# AdelinoR1.net
KiCad netlist of a schematic drawn in EAGLE
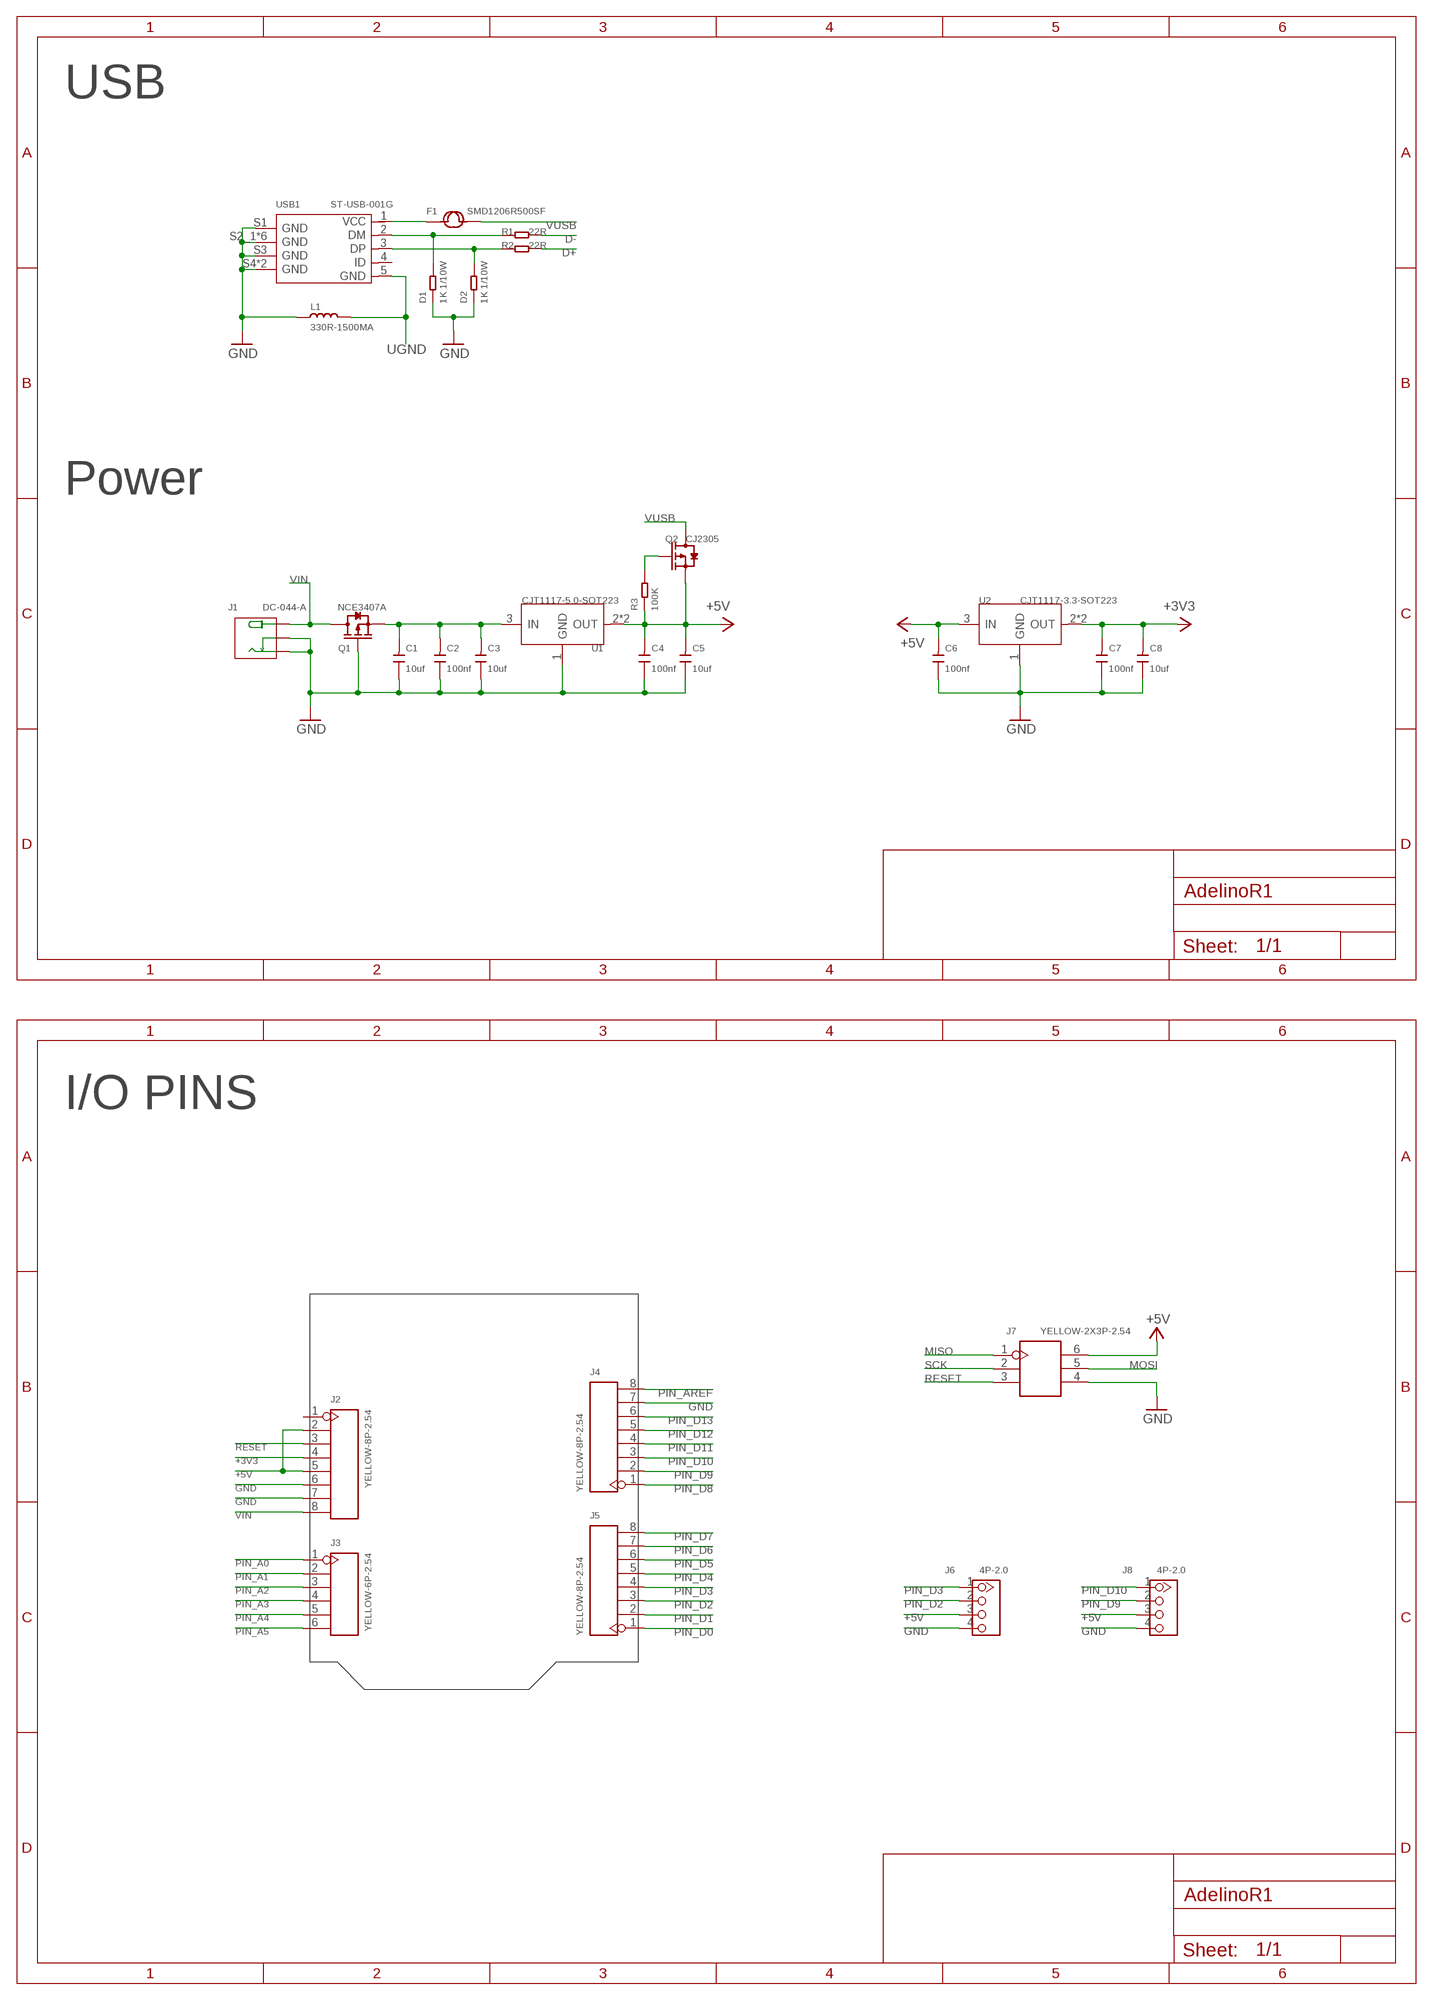
[diagram p0: schematic, sheet 1, part 1 of 2]
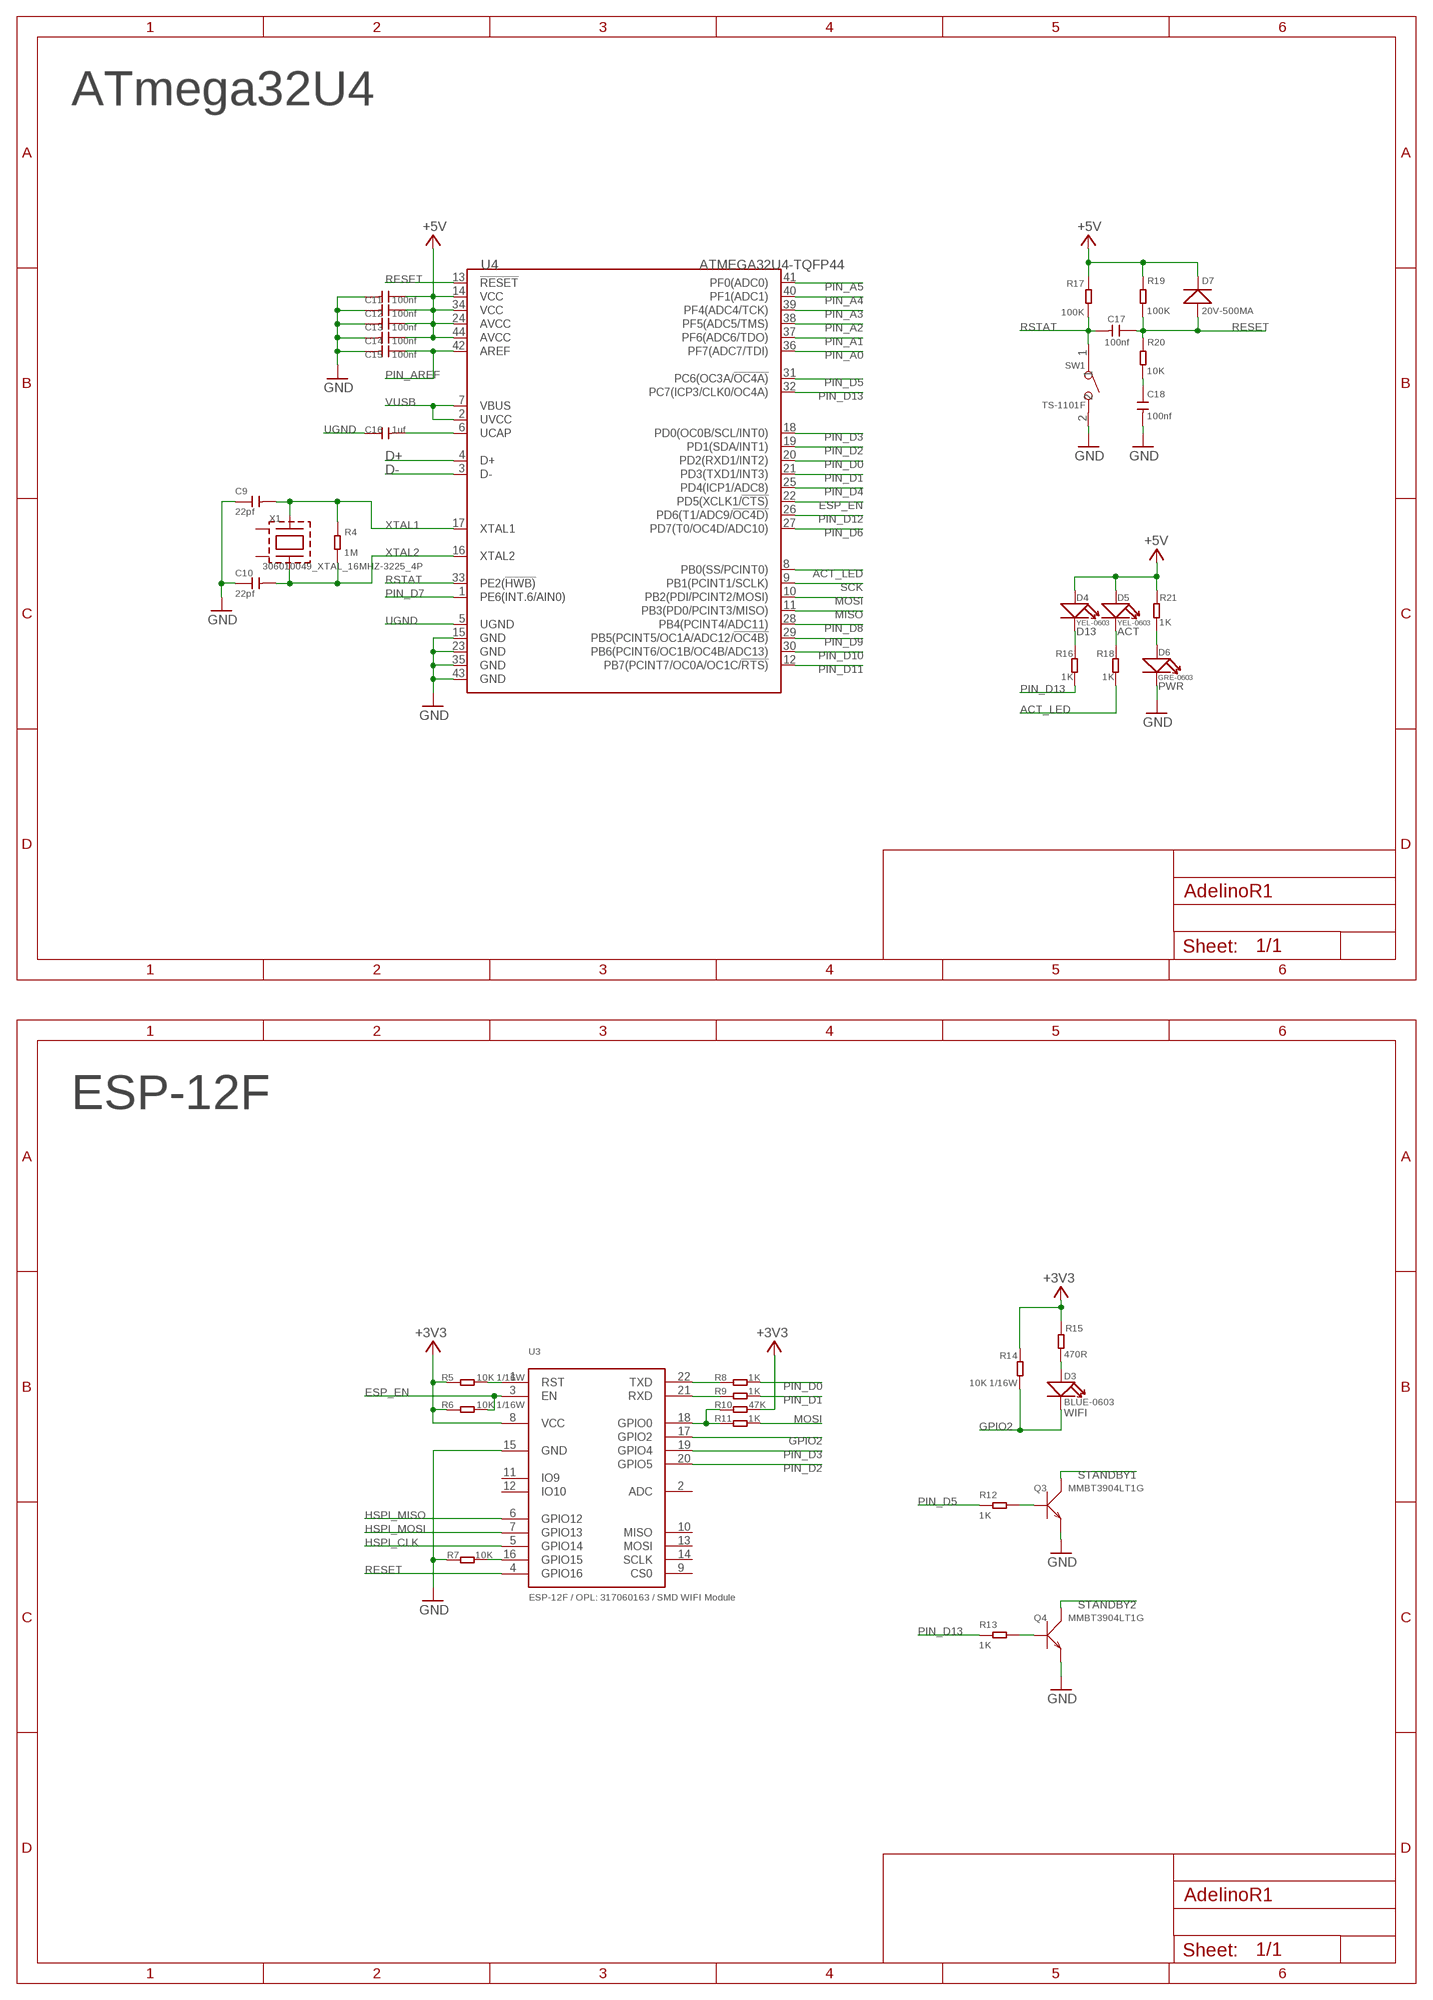
[diagram p1: schematic, sheet 1, part 2 of 2]

(export (version "E")
  (design (tool "Eeschema 10.0.6"))
  (components
    (comp (ref "C1")
      (value "10uf")
      (footprint "eagle-import:C0805")
      (fields (field (name "MPN") "CC0805KKX5R8BB106"))
      (libsource (lib "eagle-import") (part "CERAMIC-10UF-25V-10%-X5R(0805)"))
    )
    (comp (ref "C2")
      (value "100nf")
      (footprint "eagle-import:C0402")
      (fields (field (name "MPN") "CC0402KRX7R8BB104"))
      (libsource (lib "eagle-import") (part "CERAMIC-100NF-25V-10%-X7R(0402)"))
    )
    (comp (ref "C3")
      (value "10uf")
      (footprint "eagle-import:C0805")
      (fields (field (name "MPN") "CC0805KKX5R8BB106"))
      (libsource (lib "eagle-import") (part "CERAMIC-10UF-25V-10%-X5R(0805)"))
    )
    (comp (ref "C4")
      (value "100nf")
      (footprint "eagle-import:C0402")
      (fields (field (name "MPN") "CC0402KRX7R8BB104"))
      (libsource (lib "eagle-import") (part "CERAMIC-100NF-25V-10%-X7R(0402)"))
    )
    (comp (ref "C5")
      (value "10uf")
      (footprint "eagle-import:C0805")
      (fields (field (name "MPN") "CC0805KKX5R8BB106"))
      (libsource (lib "eagle-import") (part "CERAMIC-10UF-25V-10%-X5R(0805)"))
    )
    (comp (ref "C6")
      (value "100nf")
      (footprint "eagle-import:C0402")
      (fields (field (name "MPN") "CC0402KRX7R8BB104"))
      (libsource (lib "eagle-import") (part "CERAMIC-100NF-25V-10%-X7R(0402)"))
    )
    (comp (ref "C7")
      (value "100nf")
      (footprint "eagle-import:C0402")
      (fields (field (name "MPN") "CC0402KRX7R8BB104"))
      (libsource (lib "eagle-import") (part "CERAMIC-100NF-25V-10%-X7R(0402)"))
    )
    (comp (ref "C8")
      (value "10uf")
      (footprint "eagle-import:C0805")
      (fields (field (name "MPN") "CC0805KKX5R8BB106"))
      (libsource (lib "eagle-import") (part "CERAMIC-10UF-25V-10%-X5R(0805)"))
    )
    (comp (ref "C9")
      (value "22pf")
      (footprint "eagle-import:C0402")
      (fields (field (name "MPN") "CC0402JRNPO9BN220"))
      (libsource (lib "eagle-import") (part "CERAMIC-22PF-50V-5%-NPO(0402)"))
    )
    (comp (ref "C10")
      (value "22pf")
      (footprint "eagle-import:C0402")
      (fields (field (name "MPN") "CC0402JRNPO9BN220"))
      (libsource (lib "eagle-import") (part "CERAMIC-22PF-50V-5%-NPO(0402)"))
    )
    (comp (ref "C11")
      (value "100nf")
      (footprint "eagle-import:C0402")
      (fields (field (name "MPN") "CC0402KRX7R8BB104"))
      (libsource (lib "eagle-import") (part "CERAMIC-100NF-25V-10%-X7R(0402)"))
    )
    (comp (ref "C12")
      (value "100nf")
      (footprint "eagle-import:C0402")
      (fields (field (name "MPN") "CC0402KRX7R8BB104"))
      (libsource (lib "eagle-import") (part "CERAMIC-100NF-25V-10%-X7R(0402)"))
    )
    (comp (ref "C13")
      (value "100nf")
      (footprint "eagle-import:C0402")
      (fields (field (name "MPN") "CC0402KRX7R8BB104"))
      (libsource (lib "eagle-import") (part "CERAMIC-100NF-25V-10%-X7R(0402)"))
    )
    (comp (ref "C14")
      (value "100nf")
      (footprint "eagle-import:C0402")
      (fields (field (name "MPN") "CC0402KRX7R8BB104"))
      (libsource (lib "eagle-import") (part "CERAMIC-100NF-25V-10%-X7R(0402)"))
    )
    (comp (ref "C15")
      (value "100nf")
      (footprint "eagle-import:C0402")
      (fields (field (name "MPN") "CC0402KRX7R8BB104"))
      (libsource (lib "eagle-import") (part "CERAMIC-100NF-25V-10%-X7R(0402)"))
    )
    (comp (ref "C16")
      (value "1uf")
      (footprint "eagle-import:C0805")
      (fields (field (name "MPN") "CC0805KKX7R8BB105"))
      (libsource (lib "eagle-import") (part "CERAMIC-1UF-25V-10%-X7R(0805)"))
    )
    (comp (ref "C17")
      (value "100nf")
      (footprint "eagle-import:C0402")
      (fields (field (name "MPN") "CC0402KRX7R8BB104"))
      (libsource (lib "eagle-import") (part "CERAMIC-100NF-25V-10%-X7R(0402)"))
    )
    (comp (ref "C18")
      (value "100nf")
      (footprint "eagle-import:C0402")
      (fields (field (name "MPN") "CC0402KRX7R8BB104"))
      (libsource (lib "eagle-import") (part "CERAMIC-100NF-25V-10%-X7R(0402)"))
    )
    (comp (ref "D1")
      (value "1K 1/10W")
      (footprint "eagle-import:D0603")
      (fields (field (name "MPN") "RC0603JR-071KL"))
      (libsource (lib "eagle-import") (part "SMD-ESD-CG0603MLC-05E"))
    )
    (comp (ref "D2")
      (value "1K 1/10W")
      (footprint "eagle-import:D0603")
      (fields (field (name "MPN") "RC0603JR-071KL"))
      (libsource (lib "eagle-import") (part "SMD-ESD-CG0603MLC-05E"))
    )
    (comp (ref "D3")
      (value "BLUE-0603")
      (footprint "eagle-import:LED-0603")
      (fields (field (name "MPN") "19-217-BHC-ZL1M2RY-3T") (field (name "LABEL") "WIFI"))
      (libsource (lib "eagle-import") (part "SMD-LED-CLEAR-BLUE(0603)"))
    )
    (comp (ref "D4")
      (value "YEL-0603")
      (footprint "eagle-import:LED-0603")
      (fields (field (name "MPN") "19-217-Y5C-AM1N1VY-3T") (field (name "LABEL") "D13"))
      (libsource (lib "eagle-import") (part "SMD-LED-CLEAR-YELLOW(0603)"))
    )
    (comp (ref "D5")
      (value "YEL-0603")
      (footprint "eagle-import:LED-0603")
      (fields (field (name "MPN") "19-217-Y5C-AM1N1VY-3T") (field (name "LABEL") "ACT"))
      (libsource (lib "eagle-import") (part "SMD-LED-CLEAR-YELLOW(0603)"))
    )
    (comp (ref "D6")
      (value "GRE-0603")
      (footprint "eagle-import:LED-0603")
      (fields (field (name "MPN") "19-217-G7C-AN1P2-3T") (field (name "LABEL") "PWR"))
      (libsource (lib "eagle-import") (part "SMD-LED-CLEAR-GREEN(0603)"))
    )
    (comp (ref "D7")
      (value "20V-500MA")
      (footprint "eagle-import:SOD-123")
      (fields (field (name "MPN") "MBR0520LT1G"))
      (libsource (lib "eagle-import") (part "SMD-DIODE-SCHOTTKY-20V-500MA(SOD-123)P"))
    )
    (comp (ref "F1")
      (value "SMD1206R500SF")
      (footprint "eagle-import:F1206")
      (libsource (lib "eagle-import") (part "SMD-PPTC-500MA(1206)"))
    )
    (comp (ref "J1")
      (value "DC-044-A")
      (footprint "eagle-import:DCJ3P-11.6X9.6X7.0MM")
      (fields (field (name "MPN") "JACK-DC-044-A"))
      (libsource (lib "eagle-import") (part "JACK-DC-044-A"))
    )
    (comp (ref "J2")
      (value "YELLOW-8P-2.54")
      (footprint "eagle-import:H8-2.54")
      (fields (field (name "MPN") "F185-1108A1BSYC1"))
      (libsource (lib "eagle-import") (part "DIP-YELLOW-FEMALE-HEADER(8P-2.54)"))
    )
    (comp (ref "J3")
      (value "YELLOW-6P-2.54")
      (footprint "eagle-import:H6-2.54")
      (fields (field (name "MPN") "F185-1106A1BSYA3"))
      (libsource (lib "eagle-import") (part "DIP-YELLOW-FEMALE-HEADER-VERT(6P-2.54)"))
    )
    (comp (ref "J4")
      (value "YELLOW-8P-2.54")
      (footprint "eagle-import:H8-2.54")
      (fields (field (name "MPN") "F185-1108A1BSYC1"))
      (libsource (lib "eagle-import") (part "DIP-YELLOW-FEMALE-HEADER(8P-2.54)"))
    )
    (comp (ref "J5")
      (value "YELLOW-8P-2.54")
      (footprint "eagle-import:H8-2.54")
      (fields (field (name "MPN") "F185-1108A1BSYC1"))
      (libsource (lib "eagle-import") (part "DIP-YELLOW-FEMALE-HEADER(8P-2.54)"))
    )
    (comp (ref "J6")
      (value "4P-2.0")
      (footprint "eagle-import:HW4-2.0")
      (libsource (lib "eagle-import") (part "GROVE-CONNECTOR-DIP(4P-2.0)"))
    )
    (comp (ref "J7")
      (value "YELLOW-2X3P-2.54")
      (footprint "eagle-import:H2X3-2.54")
      (fields (field (name "MPN") "P125-1203A0BS116A2"))
      (libsource (lib "eagle-import") (part "DIP-YELLOW-MALE-HEADER-VERT(2X3P-2.54)"))
    )
    (comp (ref "J8")
      (value "4P-2.0")
      (footprint "eagle-import:HW4-2.0")
      (libsource (lib "eagle-import") (part "GROVE-CONNECTOR-DIP(4P-2.0)"))
    )
    (comp (ref "L1")
      (value "330R-1500MA")
      (footprint "eagle-import:L0805")
      (fields (field (name "MPN") "BLM21PG331SN1D"))
      (libsource (lib "eagle-import") (part "SMD-FERRITE-BEAD-330R-1500MA(0805)'0805'"))
    )
    (comp (ref "Q1")
      (value "NCE3407A")
      (footprint "eagle-import:SOT-23")
      (libsource (lib "eagle-import") (part "SMD-MOSFET-P-CH-VDC=30V-ID=4.3A-NCE3407A(SOT-23)"))
    )
    (comp (ref "Q2")
      (value "CJ2305")
      (footprint "eagle-import:SOT-23")
      (libsource (lib "eagle-import") (part "SMD-MOSFET-P-CH-8V-4.1A-CJ2305(SOT-23)"))
    )
    (comp (ref "Q3")
      (value "MMBT3904LT1G")
      (footprint "eagle-import:SOT-23")
      (libsource (lib "eagle-import") (part "SMD-TRANSISTORS-NPN-40V-200MA-MMBT3904LT1G(SOT-23)"))
    )
    (comp (ref "Q4")
      (value "MMBT3904LT1G")
      (footprint "eagle-import:SOT-23")
      (libsource (lib "eagle-import") (part "SMD-TRANSISTORS-NPN-40V-200MA-MMBT3904LT1G(SOT-23)"))
    )
    (comp (ref "R1")
      (value "22R")
      (footprint "eagle-import:R0402")
      (fields (field (name "MPN") "RC0402FR-0722RL"))
      (libsource (lib "eagle-import") (part "SMD-RES-22R-1%-1/16W(0402)"))
    )
    (comp (ref "R2")
      (value "22R")
      (footprint "eagle-import:R0402")
      (fields (field (name "MPN") "RC0402FR-0722RL"))
      (libsource (lib "eagle-import") (part "SMD-RES-22R-1%-1/16W(0402)"))
    )
    (comp (ref "R3")
      (value "100K")
      (footprint "eagle-import:R0402")
      (fields (field (name "MPN") "RC0402FR-07100KL"))
      (libsource (lib "eagle-import") (part "SMD-RES-100K-1%-1/16W(0402)"))
    )
    (comp (ref "R4")
      (value "1M")
      (footprint "eagle-import:R0402")
      (fields (field (name "MPN") "RC0402FR-071ML"))
      (libsource (lib "eagle-import") (part "SMD-RES-1M-1%-1/16W(0402)"))
    )
    (comp (ref "R5")
      (value "10K 1/16W")
      (footprint "eagle-import:R0402")
      (fields (field (name "MPN") "RC0402FR-0710KL"))
      (libsource (lib "eagle-import") (part "SMD-RES-10K-1%-1/16W(0402)"))
    )
    (comp (ref "R6")
      (value "10K 1/16W")
      (footprint "eagle-import:R0402")
      (fields (field (name "MPN") "RC0402FR-0710KL"))
      (libsource (lib "eagle-import") (part "SMD-RES-10K-1%-1/16W(0402)"))
    )
    (comp (ref "R7")
      (value "10K")
      (footprint "eagle-import:R0402")
      (fields (field (name "MPN") "RC0402FR-0710KL"))
      (libsource (lib "eagle-import") (part "SMD-RES-10K-1%-1/16W(0402)"))
    )
    (comp (ref "R8")
      (value "1K")
      (footprint "eagle-import:R0402")
      (fields (field (name "MPN") "RC0402JR-071KL"))
      (libsource (lib "eagle-import") (part "SMD-RES-1K-5%-1/16W(0402)"))
    )
    (comp (ref "R9")
      (value "1K")
      (footprint "eagle-import:R0402")
      (fields (field (name "MPN") "RC0402JR-071KL"))
      (libsource (lib "eagle-import") (part "SMD-RES-1K-5%-1/16W(0402)"))
    )
    (comp (ref "R10")
      (value "47K")
      (footprint "eagle-import:R0402")
      (fields (field (name "MPN") "RC0402JR-0747KL"))
      (libsource (lib "eagle-import") (part "SMD-RES-47K-5%-1/16W(0402)"))
    )
    (comp (ref "R11")
      (value "1K")
      (footprint "eagle-import:R0402")
      (fields (field (name "MPN") "RC0402JR-071KL"))
      (libsource (lib "eagle-import") (part "SMD-RES-1K-5%-1/16W(0402)"))
    )
    (comp (ref "R12")
      (value "1K")
      (footprint "eagle-import:R0402")
      (fields (field (name "MPN") "RC0402JR-071KL"))
      (libsource (lib "eagle-import") (part "SMD-RES-1K-5%-1/16W(0402)"))
    )
    (comp (ref "R13")
      (value "1K")
      (footprint "eagle-import:R0402")
      (fields (field (name "MPN") "RC0402JR-071KL"))
      (libsource (lib "eagle-import") (part "SMD-RES-1K-5%-1/16W(0402)"))
    )
    (comp (ref "R14")
      (value "10K 1/16W")
      (footprint "eagle-import:R0402")
      (fields (field (name "MPN") "RC0402FR-0710KL"))
      (libsource (lib "eagle-import") (part "SMD-RES-10K-1%-1/16W(0402)"))
    )
    (comp (ref "R15")
      (value "470R")
      (footprint "eagle-import:R0402")
      (fields (field (name "MPN") "RC0402JR-07470RL"))
      (libsource (lib "eagle-import") (part "SMD-RES-470R-5%-1/16W(0402)"))
    )
    (comp (ref "R16")
      (value "1K")
      (footprint "eagle-import:R0402")
      (fields (field (name "MPN") "RC0402JR-071KL"))
      (libsource (lib "eagle-import") (part "SMD-RES-1K-5%-1/16W(0402)"))
    )
    (comp (ref "R17")
      (value "100K")
      (footprint "eagle-import:R0402")
      (fields (field (name "MPN") "RC0402FR-07100KL"))
      (libsource (lib "eagle-import") (part "SMD-RES-100K-1%-1/16W(0402)"))
    )
    (comp (ref "R18")
      (value "1K")
      (footprint "eagle-import:R0402")
      (fields (field (name "MPN") "RC0402JR-071KL"))
      (libsource (lib "eagle-import") (part "SMD-RES-1K-5%-1/16W(0402)"))
    )
    (comp (ref "R19")
      (value "100K")
      (footprint "eagle-import:R0402")
      (fields (field (name "MPN") "RC0402FR-07100KL"))
      (libsource (lib "eagle-import") (part "SMD-RES-100K-1%-1/16W(0402)"))
    )
    (comp (ref "R20")
      (value "10K")
      (footprint "eagle-import:R0402")
      (fields (field (name "MPN") "RC0402FR-0710KL"))
      (libsource (lib "eagle-import") (part "SMD-RES-10K-1%-1/16W(0402)"))
    )
    (comp (ref "R21")
      (value "1K")
      (footprint "eagle-import:R0402")
      (fields (field (name "MPN") "RC0402JR-071KL"))
      (libsource (lib "eagle-import") (part "SMD-RES-1K-5%-1/16W(0402)"))
    )
    (comp (ref "SW1")
      (value "TS-1101F")
      (footprint "eagle-import:SW2-5.0-6.0X3.0X4.3MM")
      (libsource (lib "eagle-import") (part "DIP-BUTTON(2P-6.0X3.0X4.3MM)-TS-1101F"))
    )
    (comp (ref "U1")
      (value "CJT1117-5.0-SOT223")
      (footprint "eagle-import:SOT-223")
      (fields (field (name "MPN") "CJT1117-5.0"))
      (libsource (lib "eagle-import") (part "PMIC-CJT1117-5.0(SOT223)"))
    )
    (comp (ref "U2")
      (value "CJT1117-3.3-SOT223")
      (footprint "eagle-import:SOT-223")
      (fields (field (name "MPN") "CJT1117-3.3"))
      (libsource (lib "eagle-import") (part "PMIC-CJT1117-3.3(SOT223)"))
    )
    (comp (ref "U3")
      (value "ESP-12F / OPL: 317060163 / SMD WIFI Module")
      (footprint "eagle-import:ESP-12F")
      (libsource (lib "eagle-import") (part "ESP-12F"))
    )
    (comp (ref "U4")
      (value "ATMEGA32U4-TQFP44")
      (footprint "eagle-import:TQFP44-0.8-9.6X9.6MM")
      (fields (field (name "MPN") "ATMEGA32U4"))
      (libsource (lib "eagle-import") (part "MCU-ATMEGA32U4-AU(TQFP44)"))
    )
    (comp (ref "USB1")
      (value "ST-USB-001G")
      (footprint "eagle-import:MICRO-USB5+4P-SMD-0.65-B")
      (libsource (lib "eagle-import") (part "MICRO-USB-SMD-B-WITHOUT-POST-W/P(ST-USB-001G)"))
    )
    (comp (ref "X1")
      (value "306010049_XTAL_16MHZ-3225_4P")
      (footprint "eagle-import:X3225_4P")
      (libsource (lib "eagle-import") (part "306010049_XTAL_16MHZ-3225_4P"))
    )
  )
  (nets
    (net (code "1") (name "+3V3") (class "Default")
      (node (ref "C7") (pin "2") (pinfunction "2_2") (pintype "passive"))
      (node (ref "C8") (pin "2") (pinfunction "2_2") (pintype "passive"))
      (node (ref "J2") (pin "4") (pinfunction "4_4") (pintype "bidirectional"))
      (node (ref "R10") (pin "2") (pinfunction "2_2") (pintype "passive"))
      (node (ref "R14") (pin "2") (pinfunction "2_2") (pintype "passive"))
      (node (ref "R15") (pin "2") (pinfunction "2_2") (pintype "passive"))
      (node (ref "R5") (pin "1") (pinfunction "1_1") (pintype "passive"))
      (node (ref "R6") (pin "1") (pinfunction "1_1") (pintype "passive"))
      (node (ref "U2") (pin "2") (pinfunction "OUT_2") (pintype "bidirectional"))
      (node (ref "U2") (pin "TER") (pinfunction "OUT_TER") (pintype "bidirectional"))
      (node (ref "U3") (pin "8") (pinfunction "VCC_8") (pintype "bidirectional"))
    )
    (net (code "2") (name "+5V") (class "Default")
      (node (ref "C11") (pin "1") (pinfunction "1_1") (pintype "passive"))
      (node (ref "C12") (pin "1") (pinfunction "1_1") (pintype "passive"))
      (node (ref "C13") (pin "1") (pinfunction "1_1") (pintype "passive"))
      (node (ref "C14") (pin "1") (pinfunction "1_1") (pintype "passive"))
      (node (ref "C4") (pin "2") (pinfunction "2_2") (pintype "passive"))
      (node (ref "C5") (pin "2") (pinfunction "2_2") (pintype "passive"))
      (node (ref "C6") (pin "2") (pinfunction "2_2") (pintype "passive"))
      (node (ref "D4") (pin "+") (pinfunction "+_+") (pintype "passive"))
      (node (ref "D5") (pin "+") (pinfunction "+_+") (pintype "passive"))
      (node (ref "D7") (pin "-") (pinfunction "-_-") (pintype "passive"))
      (node (ref "J2") (pin "2") (pinfunction "2_2") (pintype "bidirectional"))
      (node (ref "J2") (pin "5") (pinfunction "5_5") (pintype "bidirectional"))
      (node (ref "J6") (pin "3") (pinfunction "3_3") (pintype "bidirectional"))
      (node (ref "J7") (pin "6") (pinfunction "6_6") (pintype "bidirectional"))
      (node (ref "J8") (pin "3") (pinfunction "3_3") (pintype "bidirectional"))
      (node (ref "Q2") (pin "2") (pinfunction "S_2") (pintype "passive"))
      (node (ref "R17") (pin "1") (pinfunction "1_1") (pintype "passive"))
      (node (ref "R19") (pin "2") (pinfunction "2_2") (pintype "passive"))
      (node (ref "R21") (pin "1") (pinfunction "1_1") (pintype "passive"))
      (node (ref "R3") (pin "1") (pinfunction "1_1") (pintype "passive"))
      (node (ref "U1") (pin "2") (pinfunction "OUT_2") (pintype "bidirectional"))
      (node (ref "U1") (pin "TER") (pinfunction "OUT_TER") (pintype "bidirectional"))
      (node (ref "U2") (pin "3") (pinfunction "IN_3") (pintype "bidirectional"))
      (node (ref "U4") (pin "14") (pinfunction "VCC_14") (pintype "bidirectional"))
      (node (ref "U4") (pin "24") (pinfunction "AVCC_24") (pintype "bidirectional"))
      (node (ref "U4") (pin "34") (pinfunction "VCC_34") (pintype "bidirectional"))
      (node (ref "U4") (pin "44") (pinfunction "AVCC_44") (pintype "bidirectional"))
    )
    (net (code "3") (name "/ACT_LED") (class "Default")
      (node (ref "R18") (pin "2") (pinfunction "2_2") (pintype "passive"))
      (node (ref "U4") (pin "8") (pinfunction "PB0(SS/PCINT0)_8") (pintype "bidirectional"))
    )
    (net (code "4") (name "/D+") (class "Default")
      (node (ref "R2") (pin "2") (pinfunction "2_2") (pintype "passive"))
      (node (ref "U4") (pin "4") (pinfunction "D+_4") (pintype "bidirectional"))
    )
    (net (code "5") (name "/D-") (class "Default")
      (node (ref "R1") (pin "2") (pinfunction "2_2") (pintype "passive"))
      (node (ref "U4") (pin "3") (pinfunction "D-_3") (pintype "bidirectional"))
    )
    (net (code "6") (name "/ESP_EN") (class "Default")
      (node (ref "R6") (pin "2") (pinfunction "2_2") (pintype "passive"))
      (node (ref "U3") (pin "3") (pinfunction "EN_3") (pintype "bidirectional"))
      (node (ref "U4") (pin "22") (pinfunction "PD5(XCLK1/~{CTS})_22") (pintype "bidirectional"))
    )
    (net (code "7") (name "/GND1") (class "Default")
      (node (ref "X1") (pin "P$2") (pinfunction "GND1_P$2") (pintype "power_in"))
    )
    (net (code "8") (name "/GND2") (class "Default")
      (node (ref "X1") (pin "P$4") (pinfunction "GND2_P$4") (pintype "power_in"))
    )
    (net (code "9") (name "/GPIO2") (class "Default")
      (node (ref "D3") (pin "-") (pinfunction "-_-") (pintype "passive"))
      (node (ref "R14") (pin "1") (pinfunction "1_1") (pintype "passive"))
      (node (ref "U3") (pin "17") (pinfunction "GPIO2_17") (pintype "bidirectional"))
    )
    (net (code "10") (name "/HSPI_CLK") (class "Default")
      (node (ref "U3") (pin "5") (pinfunction "GPIO14_5") (pintype "bidirectional"))
    )
    (net (code "11") (name "/HSPI_MISO") (class "Default")
      (node (ref "U3") (pin "6") (pinfunction "GPIO12_6") (pintype "bidirectional"))
    )
    (net (code "12") (name "/HSPI_MOSI") (class "Default")
      (node (ref "U3") (pin "7") (pinfunction "GPIO13_7") (pintype "bidirectional"))
    )
    (net (code "13") (name "/MISO") (class "Default")
      (node (ref "J7") (pin "1") (pinfunction "1_1") (pintype "bidirectional"))
      (node (ref "U4") (pin "11") (pinfunction "PB3(PD0/PCINT3/MISO)_11") (pintype "bidirectional"))
    )
    (net (code "14") (name "/MOSI") (class "Default")
      (node (ref "J7") (pin "5") (pinfunction "5_5") (pintype "bidirectional"))
      (node (ref "R11") (pin "2") (pinfunction "2_2") (pintype "passive"))
      (node (ref "U4") (pin "10") (pinfunction "PB2(PDI/PCINT2/MOSI)_10") (pintype "bidirectional"))
    )
    (net (code "15") (name "/PIN_A0") (class "Default")
      (node (ref "J3") (pin "1") (pinfunction "1_1") (pintype "bidirectional"))
      (node (ref "U4") (pin "36") (pinfunction "PF7(ADC7/TDI)_36") (pintype "bidirectional"))
    )
    (net (code "16") (name "/PIN_A1") (class "Default")
      (node (ref "J3") (pin "2") (pinfunction "2_2") (pintype "bidirectional"))
      (node (ref "U4") (pin "37") (pinfunction "PF6(ADC6/TDO)_37") (pintype "bidirectional"))
    )
    (net (code "17") (name "/PIN_A2") (class "Default")
      (node (ref "J3") (pin "3") (pinfunction "3_3") (pintype "bidirectional"))
      (node (ref "U4") (pin "38") (pinfunction "PF5(ADC5/TMS)_38") (pintype "bidirectional"))
    )
    (net (code "18") (name "/PIN_A3") (class "Default")
      (node (ref "J3") (pin "4") (pinfunction "4_4") (pintype "bidirectional"))
      (node (ref "U4") (pin "39") (pinfunction "PF4(ADC4/TCK)_39") (pintype "bidirectional"))
    )
    (net (code "19") (name "/PIN_A4") (class "Default")
      (node (ref "J3") (pin "5") (pinfunction "5_5") (pintype "bidirectional"))
      (node (ref "U4") (pin "40") (pinfunction "PF1(ADC1)_40") (pintype "bidirectional"))
    )
    (net (code "20") (name "/PIN_A5") (class "Default")
      (node (ref "J3") (pin "6") (pinfunction "6_6") (pintype "bidirectional"))
      (node (ref "U4") (pin "41") (pinfunction "PF0(ADC0)_41") (pintype "bidirectional"))
    )
    (net (code "21") (name "/PIN_AREF") (class "Default")
      (node (ref "C15") (pin "1") (pinfunction "1_1") (pintype "passive"))
      (node (ref "J4") (pin "8") (pinfunction "8_8") (pintype "bidirectional"))
      (node (ref "U4") (pin "42") (pinfunction "AREF_42") (pintype "bidirectional"))
    )
    (net (code "22") (name "/PIN_D0") (class "Default")
      (node (ref "J5") (pin "1") (pinfunction "1_1") (pintype "bidirectional"))
      (node (ref "R8") (pin "2") (pinfunction "2_2") (pintype "passive"))
      (node (ref "U4") (pin "20") (pinfunction "PD2(RXD1/INT2)_20") (pintype "bidirectional"))
    )
    (net (code "23") (name "/PIN_D1") (class "Default")
      (node (ref "J5") (pin "2") (pinfunction "2_2") (pintype "bidirectional"))
      (node (ref "R9") (pin "2") (pinfunction "2_2") (pintype "passive"))
      (node (ref "U4") (pin "21") (pinfunction "PD3(TXD1/INT3)_21") (pintype "bidirectional"))
    )
    (net (code "24") (name "/PIN_D2") (class "Default")
      (node (ref "J5") (pin "3") (pinfunction "3_3") (pintype "bidirectional"))
      (node (ref "J6") (pin "2") (pinfunction "2_2") (pintype "bidirectional"))
      (node (ref "U3") (pin "20") (pinfunction "GPIO5_20") (pintype "bidirectional"))
      (node (ref "U4") (pin "19") (pinfunction "PD1(SDA/INT1)_19") (pintype "bidirectional"))
    )
    (net (code "25") (name "/PIN_D3") (class "Default")
      (node (ref "J5") (pin "4") (pinfunction "4_4") (pintype "bidirectional"))
      (node (ref "J6") (pin "1") (pinfunction "1_1") (pintype "bidirectional"))
      (node (ref "U3") (pin "19") (pinfunction "GPIO4_19") (pintype "bidirectional"))
      (node (ref "U4") (pin "18") (pinfunction "PD0(OC0B/SCL/INT0)_18") (pintype "bidirectional"))
    )
    (net (code "26") (name "/PIN_D4") (class "Default")
      (node (ref "J5") (pin "5") (pinfunction "5_5") (pintype "bidirectional"))
      (node (ref "U4") (pin "25") (pinfunction "PD4(ICP1/ADC8)_25") (pintype "bidirectional"))
    )
    (net (code "27") (name "/PIN_D5") (class "Default")
      (node (ref "J5") (pin "6") (pinfunction "6_6") (pintype "bidirectional"))
      (node (ref "R12") (pin "1") (pinfunction "1_1") (pintype "passive"))
      (node (ref "U4") (pin "31") (pinfunction "PC6(OC3A/~{OC4A})_31") (pintype "bidirectional"))
    )
    (net (code "28") (name "/PIN_D6") (class "Default")
      (node (ref "J5") (pin "7") (pinfunction "7_7") (pintype "bidirectional"))
      (node (ref "U4") (pin "27") (pinfunction "PD7(T0/OC4D/ADC10)_27") (pintype "bidirectional"))
    )
    (net (code "29") (name "/PIN_D7") (class "Default")
      (node (ref "J5") (pin "8") (pinfunction "8_8") (pintype "bidirectional"))
      (node (ref "U4") (pin "1") (pinfunction "PE6(INT.6/AIN0)_1") (pintype "bidirectional"))
    )
    (net (code "30") (name "/PIN_D8") (class "Default")
      (node (ref "J4") (pin "1") (pinfunction "1_1") (pintype "bidirectional"))
      (node (ref "U4") (pin "28") (pinfunction "PB4(PCINT4/ADC11)_28") (pintype "bidirectional"))
    )
    (net (code "31") (name "/PIN_D9") (class "Default")
      (node (ref "J4") (pin "2") (pinfunction "2_2") (pintype "bidirectional"))
      (node (ref "J8") (pin "2") (pinfunction "2_2") (pintype "bidirectional"))
      (node (ref "U4") (pin "29") (pinfunction "PB5(PCINT5/OC1A/ADC12/~{OC4B})_29") (pintype "bidirectional"))
    )
    (net (code "32") (name "/PIN_D10") (class "Default")
      (node (ref "J4") (pin "3") (pinfunction "3_3") (pintype "bidirectional"))
      (node (ref "J8") (pin "1") (pinfunction "1_1") (pintype "bidirectional"))
      (node (ref "U4") (pin "30") (pinfunction "PB6(PCINT6/OC1B/OC4B/ADC13)_30") (pintype "bidirectional"))
    )
    (net (code "33") (name "/PIN_D11") (class "Default")
      (node (ref "J4") (pin "4") (pinfunction "4_4") (pintype "bidirectional"))
      (node (ref "U4") (pin "12") (pinfunction "PB7(PCINT7/OC0A/OC1C/~{RTS})_12") (pintype "bidirectional"))
    )
    (net (code "34") (name "/PIN_D12") (class "Default")
      (node (ref "J4") (pin "5") (pinfunction "5_5") (pintype "bidirectional"))
      (node (ref "U4") (pin "26") (pinfunction "PD6(T1/ADC9/~{OC4D})_26") (pintype "bidirectional"))
    )
    (net (code "35") (name "/PIN_D13") (class "Default")
      (node (ref "J4") (pin "6") (pinfunction "6_6") (pintype "bidirectional"))
      (node (ref "R13") (pin "1") (pinfunction "1_1") (pintype "passive"))
      (node (ref "R16") (pin "2") (pinfunction "2_2") (pintype "passive"))
      (node (ref "U4") (pin "32") (pinfunction "PC7(ICP3/CLK0/OC4A)_32") (pintype "bidirectional"))
    )
    (net (code "36") (name "/RESET") (class "Default")
      (node (ref "C17") (pin "1") (pinfunction "1_1") (pintype "passive"))
      (node (ref "D7") (pin "+") (pinfunction "+_+") (pintype "passive"))
      (node (ref "J2") (pin "3") (pinfunction "3_3") (pintype "bidirectional"))
      (node (ref "J7") (pin "3") (pinfunction "3_3") (pintype "bidirectional"))
      (node (ref "R19") (pin "1") (pinfunction "1_1") (pintype "passive"))
      (node (ref "R20") (pin "1") (pinfunction "1_1") (pintype "passive"))
      (node (ref "U3") (pin "4") (pinfunction "GPIO16_4") (pintype "bidirectional"))
      (node (ref "U4") (pin "13") (pinfunction "~{RESET}_13") (pintype "bidirectional"))
    )
    (net (code "37") (name "/RSTAT") (class "Default")
      (node (ref "C17") (pin "2") (pinfunction "2_2") (pintype "passive"))
      (node (ref "R17") (pin "2") (pinfunction "2_2") (pintype "passive"))
      (node (ref "SW1") (pin "1") (pinfunction "1_1") (pintype "bidirectional"))
      (node (ref "U4") (pin "33") (pinfunction "PE2(~{HWB})_33") (pintype "bidirectional"))
    )
    (net (code "38") (name "/SCK") (class "Default")
      (node (ref "J7") (pin "2") (pinfunction "2_2") (pintype "bidirectional"))
      (node (ref "U4") (pin "9") (pinfunction "PB1(PCINT1/SCLK)_9") (pintype "bidirectional"))
    )
    (net (code "39") (name "/STANDBY1") (class "Default")
      (node (ref "Q3") (pin "3") (pinfunction "C_3") (pintype "passive"))
    )
    (net (code "40") (name "/STANDBY2") (class "Default")
      (node (ref "Q4") (pin "3") (pinfunction "C_3") (pintype "passive"))
    )
    (net (code "41") (name "/UGND") (class "Default")
      (node (ref "C16") (pin "1") (pinfunction "1_1") (pintype "passive"))
      (node (ref "L1") (pin "2") (pinfunction "2_2") (pintype "passive"))
      (node (ref "U4") (pin "5") (pinfunction "UGND_5") (pintype "bidirectional"))
      (node (ref "USB1") (pin "5") (pinfunction "GND_5") (pintype "bidirectional"))
    )
    (net (code "42") (name "/VIN") (class "Default")
      (node (ref "J1") (pin "VCC1") (pinfunction "+_VCC1") (pintype "bidirectional"))
      (node (ref "J1") (pin "VCC2") (pinfunction "+_VCC2") (pintype "bidirectional"))
      (node (ref "J1") (pin "VCC3") (pinfunction "+_VCC3") (pintype "bidirectional"))
      (node (ref "J1") (pin "VCC4") (pinfunction "+_VCC4") (pintype "bidirectional"))
      (node (ref "J2") (pin "8") (pinfunction "8_8") (pintype "bidirectional"))
      (node (ref "Q1") (pin "3") (pinfunction "D_3") (pintype "passive"))
    )
    (net (code "43") (name "/VUSB") (class "Default")
      (node (ref "F1") (pin "2") (pinfunction "2_2") (pintype "bidirectional"))
      (node (ref "Q2") (pin "3") (pinfunction "D_3") (pintype "passive"))
      (node (ref "U4") (pin "2") (pinfunction "UVCC_2") (pintype "bidirectional"))
      (node (ref "U4") (pin "7") (pinfunction "VBUS_7") (pintype "bidirectional"))
    )
    (net (code "44") (name "/XTAL1") (class "Default")
      (node (ref "C9") (pin "2") (pinfunction "2_2") (pintype "passive"))
      (node (ref "R4") (pin "2") (pinfunction "2_2") (pintype "passive"))
      (node (ref "U4") (pin "17") (pinfunction "XTAL1_17") (pintype "bidirectional"))
      (node (ref "X1") (pin "P$1") (pinfunction "P$1_P$1") (pintype "passive"))
    )
    (net (code "45") (name "/XTAL2") (class "Default")
      (node (ref "C10") (pin "2") (pinfunction "2_2") (pintype "passive"))
      (node (ref "R4") (pin "1") (pinfunction "1_1") (pintype "passive"))
      (node (ref "U4") (pin "16") (pinfunction "XTAL2_16") (pintype "bidirectional"))
      (node (ref "X1") (pin "P$3") (pinfunction "P$2_P$3") (pintype "passive"))
    )
    (net (code "46") (name "GND") (class "Default")
      (node (ref "C1") (pin "1") (pinfunction "1_1") (pintype "passive"))
      (node (ref "C10") (pin "1") (pinfunction "1_1") (pintype "passive"))
      (node (ref "C11") (pin "2") (pinfunction "2_2") (pintype "passive"))
      (node (ref "C12") (pin "2") (pinfunction "2_2") (pintype "passive"))
      (node (ref "C13") (pin "2") (pinfunction "2_2") (pintype "passive"))
      (node (ref "C14") (pin "2") (pinfunction "2_2") (pintype "passive"))
      (node (ref "C15") (pin "2") (pinfunction "2_2") (pintype "passive"))
      (node (ref "C18") (pin "2") (pinfunction "2_2") (pintype "passive"))
      (node (ref "C2") (pin "1") (pinfunction "1_1") (pintype "passive"))
      (node (ref "C3") (pin "1") (pinfunction "1_1") (pintype "passive"))
      (node (ref "C4") (pin "1") (pinfunction "1_1") (pintype "passive"))
      (node (ref "C5") (pin "1") (pinfunction "1_1") (pintype "passive"))
      (node (ref "C6") (pin "1") (pinfunction "1_1") (pintype "passive"))
      (node (ref "C7") (pin "1") (pinfunction "1_1") (pintype "passive"))
      (node (ref "C8") (pin "1") (pinfunction "1_1") (pintype "passive"))
      (node (ref "C9") (pin "1") (pinfunction "1_1") (pintype "passive"))
      (node (ref "D1") (pin "1") (pinfunction "1_1") (pintype "passive"))
      (node (ref "D2") (pin "1") (pinfunction "1_1") (pintype "passive"))
      (node (ref "D6") (pin "-") (pinfunction "-_-") (pintype "passive"))
      (node (ref "J1") (pin "CDN1") (pinfunction "CDN_CDN1") (pintype "bidirectional"))
      (node (ref "J1") (pin "CDN2") (pinfunction "CDN_CDN2") (pintype "bidirectional"))
      (node (ref "J1") (pin "CDN3") (pinfunction "CDN_CDN3") (pintype "bidirectional"))
      (node (ref "J1") (pin "CDN4") (pinfunction "CDN_CDN4") (pintype "bidirectional"))
      (node (ref "J1") (pin "GND1") (pinfunction "-_GND1") (pintype "bidirectional"))
      (node (ref "J1") (pin "GND2") (pinfunction "-_GND2") (pintype "bidirectional"))
      (node (ref "J1") (pin "GND3") (pinfunction "-_GND3") (pintype "bidirectional"))
      (node (ref "J1") (pin "GND4") (pinfunction "-_GND4") (pintype "bidirectional"))
      (node (ref "J2") (pin "6") (pinfunction "6_6") (pintype "bidirectional"))
      (node (ref "J2") (pin "7") (pinfunction "7_7") (pintype "bidirectional"))
      (node (ref "J4") (pin "7") (pinfunction "7_7") (pintype "bidirectional"))
      (node (ref "J6") (pin "4") (pinfunction "4_4") (pintype "bidirectional"))
      (node (ref "J7") (pin "4") (pinfunction "4_4") (pintype "bidirectional"))
      (node (ref "J8") (pin "4") (pinfunction "4_4") (pintype "bidirectional"))
      (node (ref "L1") (pin "1") (pinfunction "1_1") (pintype "passive"))
      (node (ref "Q1") (pin "1") (pinfunction "G_1") (pintype "passive"))
      (node (ref "Q3") (pin "2") (pinfunction "E_2") (pintype "passive"))
      (node (ref "Q4") (pin "2") (pinfunction "E_2") (pintype "passive"))
      (node (ref "R7") (pin "1") (pinfunction "1_1") (pintype "passive"))
      (node (ref "SW1") (pin "2") (pinfunction "2_2") (pintype "bidirectional"))
      (node (ref "U1") (pin "1") (pinfunction "GND_1") (pintype "bidirectional"))
      (node (ref "U2") (pin "1") (pinfunction "GND_1") (pintype "bidirectional"))
      (node (ref "U3") (pin "15") (pinfunction "GND_15") (pintype "bidirectional"))
      (node (ref "U4") (pin "15") (pinfunction "GND_15") (pintype "bidirectional"))
      (node (ref "U4") (pin "23") (pinfunction "GND_23") (pintype "bidirectional"))
      (node (ref "U4") (pin "35") (pinfunction "GND_35") (pintype "bidirectional"))
      (node (ref "U4") (pin "43") (pinfunction "GND_43") (pintype "bidirectional"))
      (node (ref "USB1") (pin "S1") (pinfunction "GND_S1") (pintype "bidirectional"))
      (node (ref "USB1") (pin "S2_1") (pinfunction "GND_S2_1") (pintype "bidirectional"))
      (node (ref "USB1") (pin "S2_2") (pinfunction "GND_S2_2") (pintype "bidirectional"))
      (node (ref "USB1") (pin "S2_3") (pinfunction "GND_S2_3") (pintype "bidirectional"))
      (node (ref "USB1") (pin "S3") (pinfunction "GND_S3") (pintype "bidirectional"))
      (node (ref "USB1") (pin "S4") (pinfunction "GND_S4") (pintype "bidirectional"))
      (node (ref "USB1") (pin "S5_1") (pinfunction "GND_S5_1") (pintype "bidirectional"))
      (node (ref "USB1") (pin "S5_2") (pinfunction "GND_S5_2") (pintype "bidirectional"))
      (node (ref "USB1") (pin "S5_3") (pinfunction "GND_S5_3") (pintype "bidirectional"))
      (node (ref "USB1") (pin "S6") (pinfunction "GND_S6") (pintype "bidirectional"))
    )
    (net (code "47") (name "Net-(C18-Pad1)") (class "Default")
      (node (ref "C18") (pin "1") (pinfunction "1_1") (pintype "passive"))
      (node (ref "R20") (pin "2") (pinfunction "2_2") (pintype "passive"))
    )
    (net (code "48") (name "Net-(D3-Pad+)") (class "Default")
      (node (ref "D3") (pin "+") (pinfunction "+_+") (pintype "passive"))
      (node (ref "R15") (pin "1") (pinfunction "1_1") (pintype "passive"))
    )
    (net (code "49") (name "Net-(D4-Pad-)") (class "Default")
      (node (ref "D4") (pin "-") (pinfunction "-_-") (pintype "passive"))
      (node (ref "R16") (pin "1") (pinfunction "1_1") (pintype "passive"))
    )
    (net (code "50") (name "Net-(D5-Pad-)") (class "Default")
      (node (ref "D5") (pin "-") (pinfunction "-_-") (pintype "passive"))
      (node (ref "R18") (pin "1") (pinfunction "1_1") (pintype "passive"))
    )
    (net (code "51") (name "Net-(D6-Pad+)") (class "Default")
      (node (ref "D6") (pin "+") (pinfunction "+_+") (pintype "passive"))
      (node (ref "R21") (pin "2") (pinfunction "2_2") (pintype "passive"))
    )
    (net (code "52") (name "Net-(Q1-S)") (class "Default")
      (node (ref "C1") (pin "2") (pinfunction "2_2") (pintype "passive"))
      (node (ref "C2") (pin "2") (pinfunction "2_2") (pintype "passive"))
      (node (ref "C3") (pin "2") (pinfunction "2_2") (pintype "passive"))
      (node (ref "Q1") (pin "2") (pinfunction "S_2") (pintype "passive"))
      (node (ref "U1") (pin "3") (pinfunction "IN_3") (pintype "bidirectional"))
    )
    (net (code "53") (name "Net-(Q2-G)") (class "Default")
      (node (ref "Q2") (pin "1") (pinfunction "G_1") (pintype "passive"))
      (node (ref "R3") (pin "2") (pinfunction "2_2") (pintype "passive"))
    )
    (net (code "54") (name "Net-(Q3-B)") (class "Default")
      (node (ref "Q3") (pin "1") (pinfunction "B_1") (pintype "passive"))
      (node (ref "R12") (pin "2") (pinfunction "2_2") (pintype "passive"))
    )
    (net (code "55") (name "Net-(Q4-B)") (class "Default")
      (node (ref "Q4") (pin "1") (pinfunction "B_1") (pintype "passive"))
      (node (ref "R13") (pin "2") (pinfunction "2_2") (pintype "passive"))
    )
    (net (code "56") (name "Net-(U3-GPIO0)") (class "Default")
      (node (ref "R10") (pin "1") (pinfunction "1_1") (pintype "passive"))
      (node (ref "R11") (pin "1") (pinfunction "1_1") (pintype "passive"))
      (node (ref "U3") (pin "18") (pinfunction "GPIO0_18") (pintype "bidirectional"))
    )
    (net (code "57") (name "Net-(U3-GPIO15)") (class "Default")
      (node (ref "R7") (pin "2") (pinfunction "2_2") (pintype "passive"))
      (node (ref "U3") (pin "16") (pinfunction "GPIO15_16") (pintype "bidirectional"))
    )
    (net (code "58") (name "Net-(U3-RST)") (class "Default")
      (node (ref "R5") (pin "2") (pinfunction "2_2") (pintype "passive"))
      (node (ref "U3") (pin "1") (pinfunction "RST_1") (pintype "bidirectional"))
    )
    (net (code "59") (name "Net-(U3-RXD)") (class "Default")
      (node (ref "R9") (pin "1") (pinfunction "1_1") (pintype "passive"))
      (node (ref "U3") (pin "21") (pinfunction "RXD_21") (pintype "bidirectional"))
    )
    (net (code "60") (name "Net-(U3-TXD)") (class "Default")
      (node (ref "R8") (pin "1") (pinfunction "1_1") (pintype "passive"))
      (node (ref "U3") (pin "22") (pinfunction "TXD_22") (pintype "bidirectional"))
    )
    (net (code "61") (name "Net-(U4-UCAP)") (class "Default")
      (node (ref "C16") (pin "2") (pinfunction "2_2") (pintype "passive"))
      (node (ref "U4") (pin "6") (pinfunction "UCAP_6") (pintype "bidirectional"))
    )
    (net (code "62") (name "Net-(USB1-DM)") (class "Default")
      (node (ref "D1") (pin "2") (pinfunction "2_2") (pintype "passive"))
      (node (ref "R1") (pin "1") (pinfunction "1_1") (pintype "passive"))
      (node (ref "USB1") (pin "2") (pinfunction "DM_2") (pintype "bidirectional"))
    )
    (net (code "63") (name "Net-(USB1-DP)") (class "Default")
      (node (ref "D2") (pin "2") (pinfunction "2_2") (pintype "passive"))
      (node (ref "R2") (pin "1") (pinfunction "1_1") (pintype "passive"))
      (node (ref "USB1") (pin "3") (pinfunction "DP_3") (pintype "bidirectional"))
    )
    (net (code "64") (name "Net-(USB1-VCC)") (class "Default")
      (node (ref "F1") (pin "1") (pinfunction "1_1") (pintype "bidirectional"))
      (node (ref "USB1") (pin "1") (pinfunction "VCC_1") (pintype "bidirectional"))
    )
    (net (code "65") (name "unconnected-(J2-Pad1)") (class "Default")
      (node (ref "J2") (pin "1") (pinfunction "1_1") (pintype "bidirectional"))
    )
    (net (code "66") (name "unconnected-(U3-ADC-Pad2)") (class "Default")
      (node (ref "U3") (pin "2") (pinfunction "ADC_2") (pintype "bidirectional"))
    )
    (net (code "67") (name "unconnected-(U3-CS0-Pad9)") (class "Default")
      (node (ref "U3") (pin "9") (pinfunction "CS0_9") (pintype "bidirectional"))
    )
    (net (code "68") (name "unconnected-(U3-IO9-Pad11)") (class "Default")
      (node (ref "U3") (pin "11") (pinfunction "IO9_11") (pintype "bidirectional"))
    )
    (net (code "69") (name "unconnected-(U3-IO10-Pad12)") (class "Default")
      (node (ref "U3") (pin "12") (pinfunction "IO10_12") (pintype "bidirectional"))
    )
    (net (code "70") (name "unconnected-(U3-MISO-Pad10)") (class "Default")
      (node (ref "U3") (pin "10") (pinfunction "MISO_10") (pintype "bidirectional"))
    )
    (net (code "71") (name "unconnected-(U3-MOSI-Pad13)") (class "Default")
      (node (ref "U3") (pin "13") (pinfunction "MOSI_13") (pintype "bidirectional"))
    )
    (net (code "72") (name "unconnected-(U3-SCLK-Pad14)") (class "Default")
      (node (ref "U3") (pin "14") (pinfunction "SCLK_14") (pintype "bidirectional"))
    )
    (net (code "73") (name "unconnected-(USB1-ID-Pad4)") (class "Default")
      (node (ref "USB1") (pin "4") (pinfunction "ID_4") (pintype "bidirectional"))
    )
  )
)
